# domus-silicea_-_N2_-_ESP8266-01.net
KiCad netlist of a schematic drawn in EAGLE
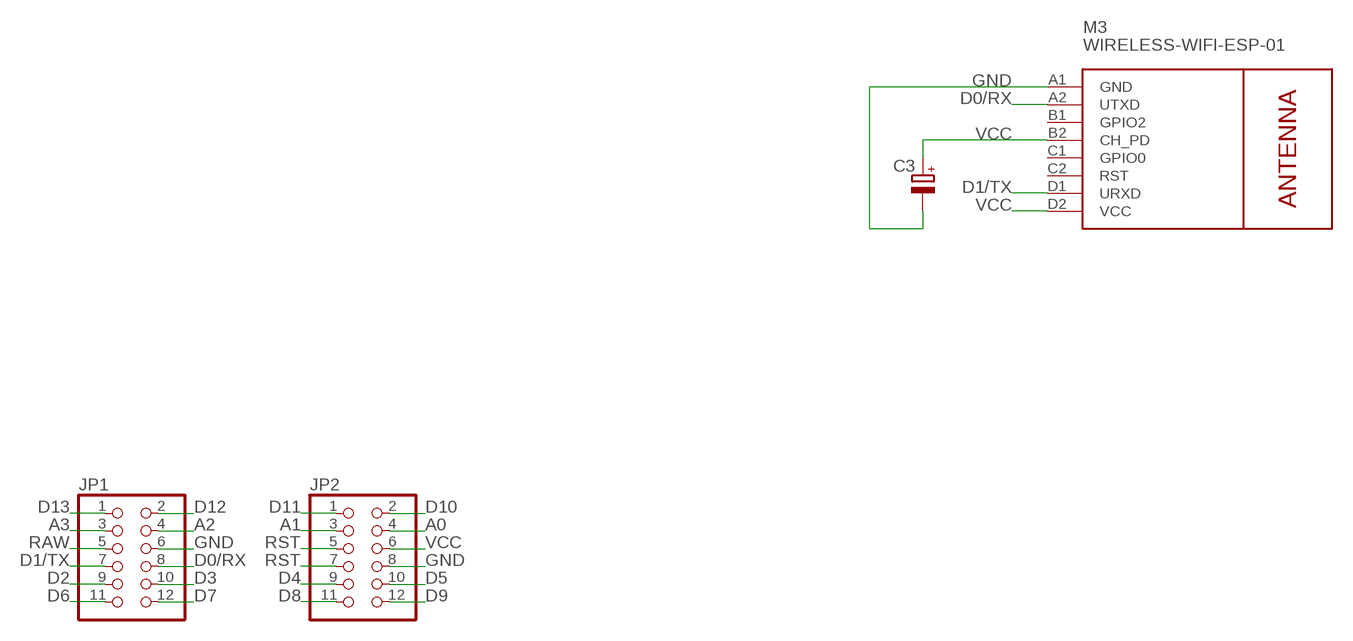
[diagram p0: schematic, sheet 1]

(export (version "E")
  (design (tool "Eeschema 10.0.6"))
  (components
    (comp (ref "C3")
      (value "CPOL-EUE2,5-6E")
      (footprint "eagle-import:E2,5-6E")
      (libsource (lib "eagle-import") (part "CPOL-EUE2,5-6E"))
    )
    (comp (ref "JP1")
      (value "PINHD-2X6")
      (footprint "eagle-import:2X06")
      (libsource (lib "eagle-import") (part "PINHD-2X6"))
    )
    (comp (ref "JP2")
      (value "PINHD-2X6")
      (footprint "eagle-import:2X06")
      (libsource (lib "eagle-import") (part "PINHD-2X6"))
    )
    (comp (ref "M3")
      (value "WIRELESS-WIFI-ESP-01")
      (footprint "eagle-import:WIRELESS-WIFI-ESP-01")
      (libsource (lib "eagle-import") (part "WIRELESS-WIFI-ESP-01"))
    )
  )
  (nets
    (net (code "1") (name "/A0") (class "Default")
      (node (ref "JP2") (pin "4") (pinfunction "4_4") (pintype "passive"))
    )
    (net (code "2") (name "/A1") (class "Default")
      (node (ref "JP2") (pin "3") (pinfunction "3_3") (pintype "passive"))
    )
    (net (code "3") (name "/A2") (class "Default")
      (node (ref "JP1") (pin "4") (pinfunction "4_4") (pintype "passive"))
    )
    (net (code "4") (name "/A3") (class "Default")
      (node (ref "JP1") (pin "3") (pinfunction "3_3") (pintype "passive"))
    )
    (net (code "5") (name "/D0{slash}RX") (class "Default")
      (node (ref "JP1") (pin "8") (pinfunction "8_8") (pintype "passive"))
      (node (ref "M3") (pin "A2") (pinfunction "UTXD_A2") (pintype "bidirectional"))
    )
    (net (code "6") (name "/D1{slash}TX") (class "Default")
      (node (ref "JP1") (pin "7") (pinfunction "7_7") (pintype "passive"))
      (node (ref "M3") (pin "D1") (pinfunction "URXD_D1") (pintype "bidirectional"))
    )
    (net (code "7") (name "/D2") (class "Default")
      (node (ref "JP1") (pin "9") (pinfunction "9_9") (pintype "passive"))
    )
    (net (code "8") (name "/D3") (class "Default")
      (node (ref "JP1") (pin "10") (pinfunction "10_10") (pintype "passive"))
    )
    (net (code "9") (name "/D4") (class "Default")
      (node (ref "JP2") (pin "9") (pinfunction "9_9") (pintype "passive"))
    )
    (net (code "10") (name "/D5") (class "Default")
      (node (ref "JP2") (pin "10") (pinfunction "10_10") (pintype "passive"))
    )
    (net (code "11") (name "/D6") (class "Default")
      (node (ref "JP1") (pin "11") (pinfunction "11_11") (pintype "passive"))
    )
    (net (code "12") (name "/D7") (class "Default")
      (node (ref "JP1") (pin "12") (pinfunction "12_12") (pintype "passive"))
    )
    (net (code "13") (name "/D8") (class "Default")
      (node (ref "JP2") (pin "11") (pinfunction "11_11") (pintype "passive"))
    )
    (net (code "14") (name "/D9") (class "Default")
      (node (ref "JP2") (pin "12") (pinfunction "12_12") (pintype "passive"))
    )
    (net (code "15") (name "/D10") (class "Default")
      (node (ref "JP2") (pin "2") (pinfunction "2_2") (pintype "passive"))
    )
    (net (code "16") (name "/D11") (class "Default")
      (node (ref "JP2") (pin "1") (pinfunction "1_1") (pintype "passive"))
    )
    (net (code "17") (name "/D12") (class "Default")
      (node (ref "JP1") (pin "2") (pinfunction "2_2") (pintype "passive"))
    )
    (net (code "18") (name "/D13") (class "Default")
      (node (ref "JP1") (pin "1") (pinfunction "1_1") (pintype "passive"))
    )
    (net (code "19") (name "/GND") (class "Default")
      (node (ref "C3") (pin "-") (pinfunction "-_-") (pintype "passive"))
      (node (ref "JP1") (pin "6") (pinfunction "6_6") (pintype "passive"))
      (node (ref "JP2") (pin "8") (pinfunction "8_8") (pintype "passive"))
      (node (ref "M3") (pin "A1") (pinfunction "GND_A1") (pintype "power_in"))
    )
    (net (code "20") (name "/RAW") (class "Default")
      (node (ref "JP1") (pin "5") (pinfunction "5_5") (pintype "passive"))
    )
    (net (code "21") (name "/RST") (class "Default")
      (node (ref "JP2") (pin "5") (pinfunction "5_5") (pintype "passive"))
      (node (ref "JP2") (pin "7") (pinfunction "7_7") (pintype "passive"))
    )
    (net (code "22") (name "/VCC") (class "Default")
      (node (ref "C3") (pin "+") (pinfunction "+_+") (pintype "passive"))
      (node (ref "JP2") (pin "6") (pinfunction "6_6") (pintype "passive"))
      (node (ref "M3") (pin "B2") (pinfunction "CH_PD_B2") (pintype "bidirectional"))
      (node (ref "M3") (pin "D2") (pinfunction "VCC_D2") (pintype "power_in"))
    )
    (net (code "23") (name "unconnected-(M3-GPIO0-PadC1)") (class "Default")
      (node (ref "M3") (pin "C1") (pinfunction "GPIO0_C1") (pintype "bidirectional"))
    )
    (net (code "24") (name "unconnected-(M3-GPIO2-PadB1)") (class "Default")
      (node (ref "M3") (pin "B1") (pinfunction "GPIO2_B1") (pintype "bidirectional"))
    )
    (net (code "25") (name "unconnected-(M3-RST-PadC2)") (class "Default")
      (node (ref "M3") (pin "C2") (pinfunction "RST_C2") (pintype "bidirectional"))
    )
  )
)
